# schematic_kcs-01r.net
KiCad netlist of a schematic drawn in EasyEDA
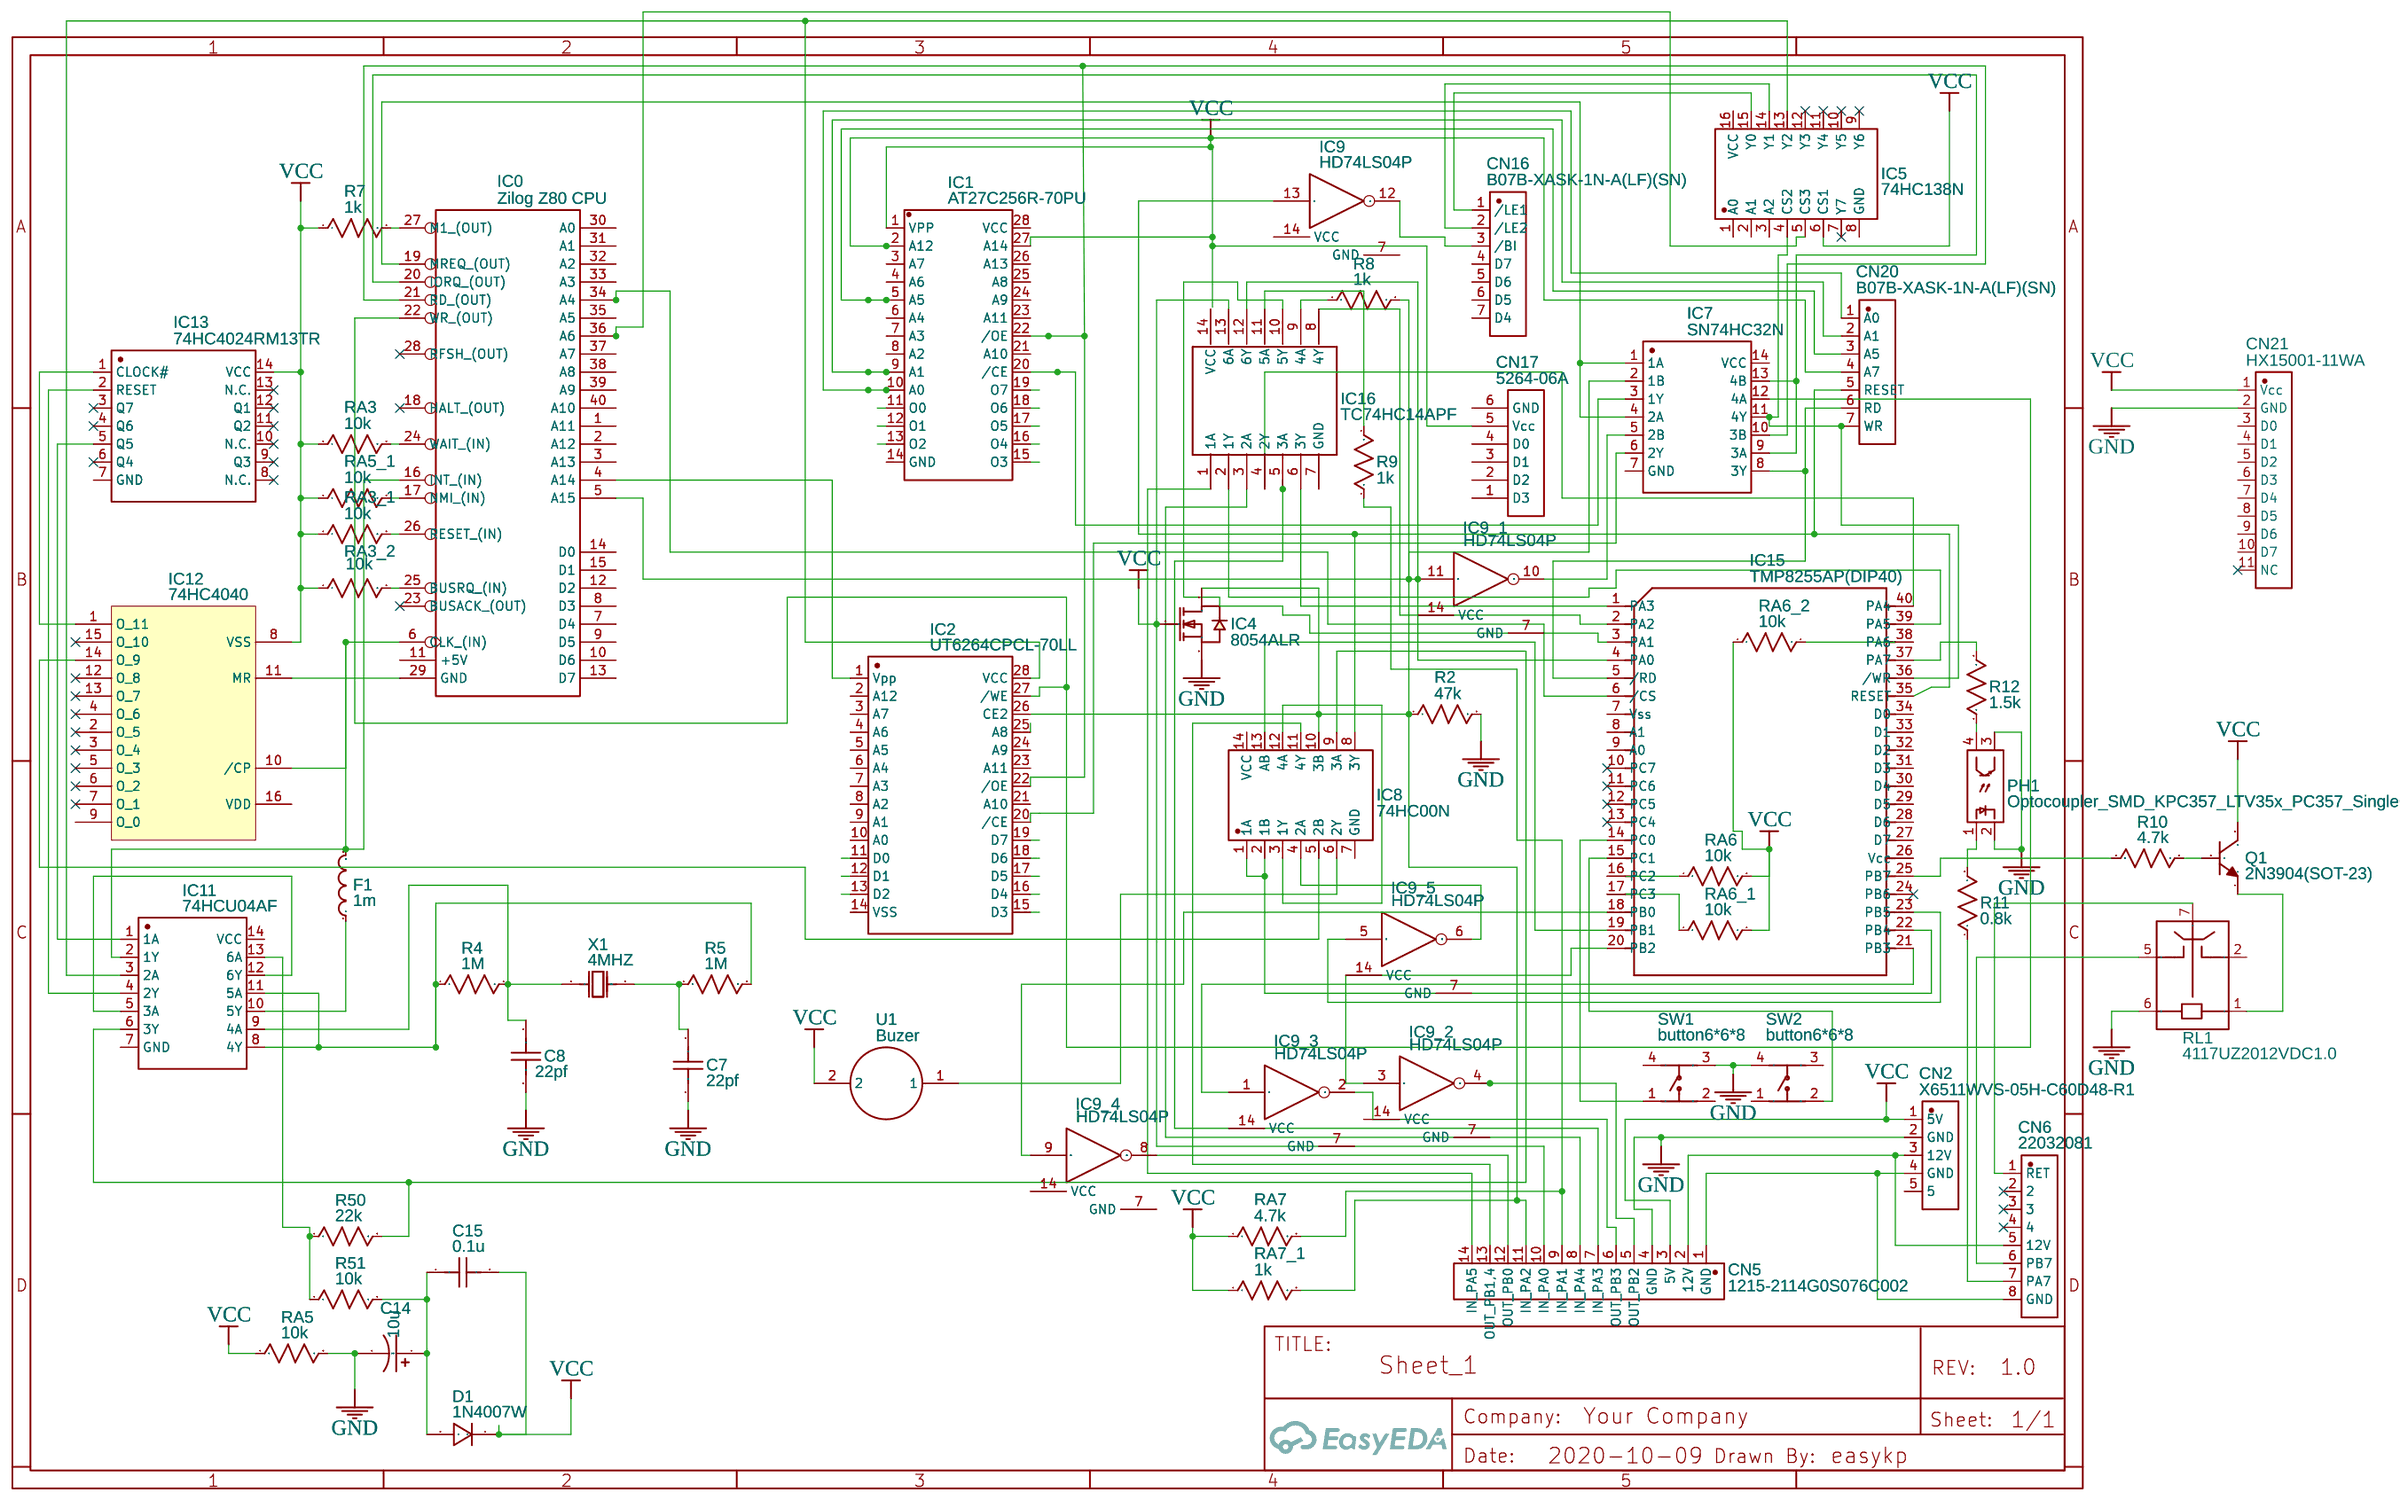
[diagram p0: schematic sheet]

(export (version "E")
  (design (tool "Eeschema 10.0.6"))
  (components
    (comp (ref "C7") (value "22pf") (libsource (lib "") (part "C_0603_US")))
    (comp (ref "C8") (value "22pf") (libsource (lib "") (part "C_0603_US")))
    (comp (ref "C14") (value "10u") (libsource (lib "") (part "C_Tan_SMD_A_US")))
    (comp (ref "C15") (value "0.1u") (libsource (lib "") (part "C_0603_US_1")))
    (comp (ref "CN2")
      (value "X6511WVS-05H-C60D48-R1")
      (fields (field (name "BOM_Supplier Part") "C780063"))
      (libsource (lib "") (part "X6511WVS-05H-C60D48-R1"))
    )
    (comp (ref "CN5")
      (value "1215-2114G0S076C002")
      (fields (field (name "BOM_Supplier Part") "C721461"))
      (libsource (lib "") (part "1215-2114G0S076C002"))
    )
    (comp (ref "CN6")
      (value "22032081")
      (fields (field (name "BOM_Supplier Part") "C586971"))
      (libsource (lib "") (part "22032081"))
    )
    (comp (ref "CN16")
      (value "B07B-XASK-1N-A(LF)(SN)")
      (fields (field (name "BOM_Supplier Part") "C378921"))
      (libsource (lib "") (part "B07B-XASK-1N-A(LF)(SN)_1"))
    )
    (comp (ref "CN17")
      (value "5264-06A")
      (fields (field (name "BOM_Supplier Part") "C40160"))
      (libsource (lib "") (part "5264-06A"))
    )
    (comp (ref "CN20")
      (value "B07B-XASK-1N-A(LF)(SN)")
      (fields (field (name "BOM_Supplier Part") "C378921"))
      (libsource (lib "") (part "B07B-XASK-1N-A(LF)(SN)"))
    )
    (comp (ref "CN21")
      (value "HX15001-11WA")
      (fields (field (name "BOM_Supplier Part") "C442136"))
      (libsource (lib "") (part "HX15001-11WA"))
    )
    (comp (ref "D1")
      (value "1N4007W")
      (fields (field (name "BOM_Supplier Part") "C328592"))
      (libsource (lib "") (part "1N4007W"))
    )
    (comp (ref "F1") (value "1m") (libsource (lib "") (part "L0603_US")))
    (comp (ref "IC0")
      (value "Zilog Z80 CPU")
      (fields (field (name "BOM_Manufacturer Part") "Zilog") (field (name "BOM_Supplier Part") "Z84C0020"))
      (libsource (lib "") (part "Zilog Z80 CPU"))
    )
    (comp (ref "IC1")
      (value "AT27C256R-70PU")
      (fields (field (name "BOM_Supplier Part") "C147880"))
      (libsource (lib "") (part "AT27C256R-70PU"))
    )
    (comp (ref "IC2")
      (value "UT6264CPCL-70LL")
      (fields (field (name "BOM_Supplier Part") "C32483"))
      (libsource (lib "") (part "UT6264CPCL-70LL"))
    )
    (comp (ref "IC4") (value "8054ALR") (libsource (lib "") (part "2N7002")))
    (comp (ref "IC5")
      (value "74HC138N")
      (fields (field (name "BOM_Supplier Part") "C507188"))
      (libsource (lib "") (part "74HC138N"))
    )
    (comp (ref "IC7")
      (value "SN74HC32N")
      (fields (field (name "BOM_Supplier Part") "C2894"))
      (libsource (lib "") (part "SN74HC32N"))
    )
    (comp (ref "IC8")
      (value "74HC00N")
      (fields (field (name "BOM_Supplier Part") "C596352"))
      (libsource (lib "") (part "74HC00N"))
    )
    (comp (ref "IC9") (value "HD74LS04P") (libsource (lib "") (part "HD74LS04P_2")))
    (comp (ref "IC9_1") (value "HD74LS04P") (libsource (lib "") (part "HD74LS04P_1")))
    (comp (ref "IC9_2") (value "HD74LS04P") (libsource (lib "") (part "HD74LS04P_5")))
    (comp (ref "IC9_3") (value "HD74LS04P") (libsource (lib "") (part "HD74LS04P")))
    (comp (ref "IC9_4") (value "HD74LS04P") (libsource (lib "") (part "HD74LS04P_4")))
    (comp (ref "IC9_5") (value "HD74LS04P") (libsource (lib "") (part "HD74LS04P_3")))
    (comp (ref "IC11")
      (value "74HCU04AF")
      (fields (field (name "BOM_Supplier Part") "C8157"))
      (libsource (lib "") (part "74HCU04AF"))
    )
    (comp (ref "IC12") (value "74HC4040") (libsource (lib "") (part "74HC4040")))
    (comp (ref "IC13")
      (value "74HC4024RM13TR")
      (fields (field (name "BOM_Supplier Part") "C5643"))
      (libsource (lib "") (part "74HC4024RM13TR"))
    )
    (comp (ref "IC15")
      (value "TMP8255AP(DIP40)")
      (fields (field (name "BOM_Manufacturer Part") "?"))
      (libsource (lib "") (part "MCU-ATMEGA32-16PU(DIP40)"))
    )
    (comp (ref "IC16") (value "TC74HC14APF") (libsource (lib "") (part "TC74HC14APF")))
    (comp (ref "PH1")
      (value "Optocoupler_SMD_KPC357_LTV35x_PC357_SingleChannel")
      (libsource (lib "") (part "Optocoupler_SMD_KPC357_LTV35x_PC357_SingleChannel"))
    )
    (comp (ref "Q1")
      (value "2N3904(SOT-23)")
      (fields
        (field (name "BOM_Manufacturer Part") "2n3904S-RTK/PS")
        (field (name "BOM_Supplier Part") "C18536")
      )
      (libsource (lib "") (part "2N3904(SOT-23)"))
    )
    (comp (ref "R2") (value "47k") (libsource (lib "") (part "R_0603_US")))
    (comp (ref "R4") (value "1M") (libsource (lib "") (part "R_0603_US")))
    (comp (ref "R5") (value "1M") (libsource (lib "") (part "R_0603_US")))
    (comp (ref "R7") (value "1k") (libsource (lib "") (part "R_0603_US")))
    (comp (ref "R8") (value "1k") (libsource (lib "") (part "R_0603_US")))
    (comp (ref "R9") (value "1k") (libsource (lib "") (part "R_0603_US_1")))
    (comp (ref "R10") (value "4.7k") (libsource (lib "") (part "R_0603_US_6")))
    (comp (ref "R11") (value "0.8k") (libsource (lib "") (part "R_0603_US_1")))
    (comp (ref "R12") (value "1.5k") (libsource (lib "") (part "R_0603_US_1")))
    (comp (ref "R50") (value "22k") (libsource (lib "") (part "R_0603_US")))
    (comp (ref "R51") (value "10k") (libsource (lib "") (part "R_0603_US")))
    (comp (ref "RA3") (value "10k") (libsource (lib "") (part "R_0603_US_5")))
    (comp (ref "RA3_1") (value "10k") (libsource (lib "") (part "R_0603_US_3")))
    (comp (ref "RA3_2") (value "10k") (libsource (lib "") (part "R_0603_US_3")))
    (comp (ref "RA5") (value "10k") (libsource (lib "") (part "R_0603_US_5")))
    (comp (ref "RA5_1") (value "10k") (libsource (lib "") (part "R_0603_US_7")))
    (comp (ref "RA6") (value "10k") (libsource (lib "") (part "R_0603_US_5")))
    (comp (ref "RA6_1") (value "10k") (libsource (lib "") (part "R_0603_US_4")))
    (comp (ref "RA6_2") (value "10k") (libsource (lib "") (part "R_0603_US_4")))
    (comp (ref "RA7") (value "4.7k") (libsource (lib "") (part "R_0603_US_5")))
    (comp (ref "RA7_1") (value "1k") (libsource (lib "") (part "R_0603_US_2")))
    (comp (ref "RL1")
      (value "4117UZ2012VDC1.0")
      (fields (field (name "BOM_Supplier Part") "C165875"))
      (libsource (lib "") (part "4117UZ2012VDC1.0"))
    )
    (comp (ref "SW1")
      (value "button6*6*8")
      (fields (field (name "BOM_Supplier Part") "C59982"))
      (libsource (lib "") (part "button6*6*8"))
    )
    (comp (ref "SW2")
      (value "button6*6*8")
      (fields (field (name "BOM_Supplier Part") "C59982"))
      (libsource (lib "") (part "button6*6*8"))
    )
    (comp (ref "U1") (value "Buzer") (libsource (lib "") (part "Buzer")))
    (comp (ref "X1")
      (value "4MHZ")
      (fields
        (field (name "BOM_Manufacturer Part") "49SAC04000202080")
        (field (name "BOM_Supplier Part") "C390748")
      )
      (libsource (lib "") (part "49SAC04000202080"))
    )
  )
  (nets
    (net (code "1") (name "GND") (class "Default")
      (node (ref "C14") (pin "2") (pinfunction "2_2") (pintype "unspecified"))
      (node (ref "C7") (pin "1") (pinfunction "1_1") (pintype "unspecified"))
      (node (ref "C8") (pin "1") (pinfunction "1_1") (pintype "unspecified"))
      (node (ref "CN2") (pin "2") (pinfunction "GND_2") (pintype "unspecified"))
      (node (ref "CN21") (pin "2") (pinfunction "GND_2") (pintype "unspecified"))
      (node (ref "CN5") (pin "4") (pinfunction "GND_4") (pintype "unspecified"))
      (node (ref "IC4") (pin "2") (pinfunction "S_2") (pintype "unspecified"))
      (node (ref "PH1") (pin "2") (pintype "unspecified"))
      (node (ref "PH1") (pin "3") (pintype "unspecified"))
      (node (ref "R2") (pin "2") (pinfunction "2_2") (pintype "unspecified"))
      (node (ref "RA5") (pin "2") (pinfunction "2_2") (pintype "unspecified"))
      (node (ref "RL1") (pin "6") (pinfunction "6_6") (pintype "unspecified"))
      (node (ref "SW1") (pin "3") (pinfunction "3_3") (pintype "unspecified"))
      (node (ref "SW2") (pin "4") (pinfunction "4_4") (pintype "unspecified"))
    )
    (net (code "2") (name "Net-(C14-Pad1)") (class "Default")
      (node (ref "C14") (pin "1") (pinfunction "1_1") (pintype "unspecified"))
      (node (ref "C15") (pin "1") (pinfunction "1_1") (pintype "unspecified"))
      (node (ref "D1") (pin "2") (pinfunction "2_2") (pintype "unspecified"))
      (node (ref "R51") (pin "2") (pinfunction "2_2") (pintype "unspecified"))
    )
    (net (code "3") (name "Net-(CN2-12V)") (class "Default")
      (node (ref "CN2") (pin "3") (pinfunction "12V_3") (pintype "unspecified"))
      (node (ref "CN5") (pin "2") (pinfunction "12V_2") (pintype "unspecified"))
      (node (ref "CN6") (pin "5") (pinfunction "12V_5") (pintype "unspecified"))
    )
    (net (code "4") (name "Net-(CN5-IN_PA1)") (class "Default")
      (node (ref "CN5") (pin "9") (pinfunction "IN_PA1_9") (pintype "unspecified"))
      (node (ref "R9") (pin "1") (pinfunction "1_1") (pintype "unspecified"))
      (node (ref "RA7") (pin "2") (pinfunction "2_2") (pintype "unspecified"))
    )
    (net (code "5") (name "Net-(CN5-IN_PA2)") (class "Default")
      (node (ref "CN5") (pin "11") (pinfunction "IN_PA2_11") (pintype "unspecified"))
      (node (ref "IC0") (pin "5") (pinfunction "A15_5") (pintype "output"))
      (node (ref "IC15") (pin "4") (pinfunction "PA0_4") (pintype "unspecified"))
      (node (ref "IC16") (pin "12") (pinfunction "6Y_12") (pintype "bidirectional"))
      (node (ref "IC2") (pin "26") (pinfunction "CE2_26") (pintype "unspecified"))
      (node (ref "IC4") (pin "3") (pinfunction "D_3") (pintype "unspecified"))
      (node (ref "IC7") (pin "2") (pinfunction "1B_2") (pintype "unspecified"))
      (node (ref "IC8") (pin "10") (pinfunction "3B_10") (pintype "unspecified"))
      (node (ref "IC9_1") (pin "11") (pinfunction "6A_11") (pintype "unspecified"))
      (node (ref "R2") (pin "1") (pinfunction "1_1") (pintype "unspecified"))
      (node (ref "R8") (pin "2") (pinfunction "2_2") (pintype "unspecified"))
      (node (ref "RA7_1") (pin "2") (pinfunction "2_2") (pintype "unspecified"))
    )
    (net (code "6") (name "Net-(CN5-IN_PA3)") (class "Default")
      (node (ref "CN5") (pin "7") (pinfunction "IN_PA3_7") (pintype "unspecified"))
      (node (ref "IC16") (pin "5") (pinfunction "3A_5") (pintype "bidirectional"))
    )
    (net (code "7") (name "Net-(CN5-IN_PA4)") (class "Default")
      (node (ref "CN5") (pin "8") (pinfunction "IN_PA4_8") (pintype "unspecified"))
      (node (ref "IC16") (pin "3") (pinfunction "2A_3") (pintype "bidirectional"))
    )
    (net (code "8") (name "Net-(CN5-IN_PA5)") (class "Default")
      (node (ref "CN5") (pin "14") (pinfunction "IN_PA5_14") (pintype "unspecified"))
      (node (ref "IC16") (pin "1") (pinfunction "1A_1") (pintype "bidirectional"))
    )
    (net (code "9") (name "Net-(CN5-OUT_PB0)") (class "Default")
      (node (ref "CN5") (pin "12") (pinfunction "OUT_PB0_12") (pintype "unspecified"))
      (node (ref "IC9_4") (pin "8") (pinfunction "6Y_8") (pintype "output"))
    )
    (net (code "10") (name "Net-(CN5-OUT_PB1,4)") (class "Default")
      (node (ref "CN5") (pin "13") (pinfunction "OUT_PB1,4_13") (pintype "unspecified"))
      (node (ref "IC8") (pin "11") (pinfunction "4Y_11") (pintype "unspecified"))
    )
    (net (code "11") (name "Net-(CN5-OUT_PB2)") (class "Default")
      (node (ref "CN5") (pin "5") (pinfunction "OUT_PB2_5") (pintype "unspecified"))
      (node (ref "IC9_2") (pin "4") (pinfunction "6Y_4") (pintype "output"))
    )
    (net (code "12") (name "Net-(CN5-OUT_PB3)") (class "Default")
      (node (ref "CN5") (pin "6") (pinfunction "OUT_PB3_6") (pintype "unspecified"))
      (node (ref "IC9_3") (pin "2") (pinfunction "6Y_2") (pintype "output"))
    )
    (net (code "13") (name "Net-(CN6-GND)") (class "Default")
      (node (ref "CN2") (pin "4") (pinfunction "GND_4") (pintype "unspecified"))
      (node (ref "CN5") (pin "1") (pinfunction "GND_1") (pintype "unspecified"))
      (node (ref "CN6") (pin "8") (pinfunction "GND_8") (pintype "unspecified"))
    )
    (net (code "14") (name "Net-(CN6-PA7)") (class "Default")
      (node (ref "CN6") (pin "7") (pinfunction "PA7_7") (pintype "unspecified"))
      (node (ref "R11") (pin "1") (pinfunction "1_1") (pintype "unspecified"))
    )
    (net (code "15") (name "Net-(CN6-PB7)") (class "Default")
      (node (ref "CN6") (pin "6") (pinfunction "PB7_6") (pintype "unspecified"))
      (node (ref "RL1") (pin "5") (pinfunction "5_5") (pintype "unspecified"))
    )
    (net (code "16") (name "Net-(CN6-RET)") (class "Default")
      (node (ref "CN6") (pin "1") (pinfunction "RET_1") (pintype "unspecified"))
      (node (ref "RL1") (pin "7") (pinfunction "7_7") (pintype "unspecified"))
    )
    (net (code "17") (name "Net-(CN16-{slash}BI)") (class "Default")
      (node (ref "CN16") (pin "3") (pinfunction "/BI_3") (pintype "unspecified"))
      (node (ref "IC9") (pin "12") (pinfunction "6Y_12") (pintype "output"))
    )
    (net (code "18") (name "Net-(CN16-{slash}LE1)") (class "Default")
      (node (ref "CN16") (pin "1") (pinfunction "/LE1_1") (pintype "unspecified"))
      (node (ref "IC5") (pin "15") (pinfunction "Y0_15") (pintype "unspecified"))
    )
    (net (code "19") (name "Net-(CN16-{slash}LE2)") (class "Default")
      (node (ref "CN16") (pin "2") (pinfunction "/LE2_2") (pintype "unspecified"))
      (node (ref "IC5") (pin "14") (pinfunction "Y1_14") (pintype "unspecified"))
    )
    (net (code "20") (name "Net-(CN20-A0)") (class "Default")
      (node (ref "CN20") (pin "1") (pinfunction "A0_1") (pintype "unspecified"))
      (node (ref "IC1") (pin "10") (pinfunction "A0_10") (pintype "unspecified"))
    )
    (net (code "21") (name "Net-(CN20-A1)") (class "Default")
      (node (ref "CN20") (pin "2") (pinfunction "A1_2") (pintype "unspecified"))
      (node (ref "IC1") (pin "9") (pinfunction "A1_9") (pintype "unspecified"))
    )
    (net (code "22") (name "Net-(CN20-A5)") (class "Default")
      (node (ref "CN20") (pin "3") (pinfunction "A5_3") (pintype "unspecified"))
      (node (ref "IC1") (pin "5") (pinfunction "A5_5") (pintype "unspecified"))
    )
    (net (code "23") (name "Net-(CN20-RD)") (class "Default")
      (node (ref "CN20") (pin "6") (pinfunction "RD_6") (pintype "unspecified"))
      (node (ref "IC15") (pin "5") (pinfunction "/RD_5") (pintype "unspecified"))
      (node (ref "IC7") (pin "8") (pinfunction "3Y_8") (pintype "unspecified"))
    )
    (net (code "24") (name "Net-(CN20-RESET)") (class "Default")
      (node (ref "CN20") (pin "5") (pinfunction "RESET_5") (pintype "unspecified"))
      (node (ref "IC15") (pin "35") (pinfunction "RESET_35") (pintype "unspecified"))
      (node (ref "IC8") (pin "8") (pinfunction "3Y_8") (pintype "unspecified"))
      (node (ref "IC9") (pin "13") (pinfunction "6A_13") (pintype "unspecified"))
    )
    (net (code "25") (name "Net-(CN20-WR)") (class "Default")
      (node (ref "CN20") (pin "7") (pinfunction "WR_7") (pintype "unspecified"))
      (node (ref "IC0") (pin "36") (pinfunction "A6_36") (pintype "output"))
      (node (ref "IC15") (pin "36") (pinfunction "/WR_36") (pintype "unspecified"))
      (node (ref "IC5") (pin "4") (pinfunction "CS2_4") (pintype "unspecified"))
      (node (ref "IC5") (pin "5") (pinfunction "CS3_5") (pintype "unspecified"))
      (node (ref "IC7") (pin "11") (pinfunction "4Y_11") (pintype "unspecified"))
    )
    (net (code "26") (name "Net-(IC0-A4)") (class "Default")
      (node (ref "IC0") (pin "34") (pinfunction "A4_34") (pintype "output"))
      (node (ref "IC15") (pin "6") (pinfunction "/CS_6") (pintype "unspecified"))
    )
    (net (code "27") (name "Net-(IC0-A14)") (class "Default")
      (node (ref "IC0") (pin "4") (pinfunction "A14_4") (pintype "output"))
      (node (ref "IC2") (pin "1") (pinfunction "Vpp_1") (pintype "unspecified"))
    )
    (net (code "28") (name "Net-(IC0-BUSRQ_(IN))") (class "Default")
      (node (ref "IC0") (pin "25") (pinfunction "BUSRQ_(IN)_25") (pintype "input"))
      (node (ref "RA3_2") (pin "2") (pinfunction "2_2") (pintype "unspecified"))
    )
    (net (code "29") (name "Net-(IC0-CLK_(IN))") (class "Default")
      (node (ref "F1") (pin "2") (pinfunction "2_2") (pintype "unspecified"))
      (node (ref "IC0") (pin "16") (pinfunction "INT_(IN)_16") (pintype "input"))
      (node (ref "IC0") (pin "6") (pinfunction "CLK_(IN)_6") (pintype "input"))
      (node (ref "IC11") (pin "2") (pinfunction "1Y_2") (pintype "unspecified"))
      (node (ref "IC12") (pin "10") (pinfunction "/CP_10") (pintype "unspecified"))
    )
    (net (code "30") (name "Net-(IC0-GND)") (class "Default")
      (node (ref "IC0") (pin "29") (pinfunction "GND_29") (pintype "passive"))
      (node (ref "IC12") (pin "11") (pinfunction "MR_11") (pintype "unspecified"))
    )
    (net (code "31") (name "Net-(IC0-IORQ_(OUT))") (class "Default")
      (node (ref "IC0") (pin "20") (pinfunction "IORQ_(OUT)_20") (pintype "output"))
      (node (ref "IC7") (pin "13") (pinfunction "4B_13") (pintype "unspecified"))
      (node (ref "IC7") (pin "9") (pinfunction "3A_9") (pintype "unspecified"))
    )
    (net (code "32") (name "Net-(IC0-M1_(OUT))") (class "Default")
      (node (ref "IC0") (pin "27") (pinfunction "M1_(OUT)_27") (pintype "output"))
      (node (ref "R7") (pin "2") (pinfunction "2_2") (pintype "unspecified"))
    )
    (net (code "33") (name "Net-(IC0-MREQ_(OUT))") (class "Default")
      (node (ref "IC0") (pin "19") (pinfunction "MREQ_(OUT)_19") (pintype "output"))
      (node (ref "IC7") (pin "1") (pinfunction "1A_1") (pintype "unspecified"))
      (node (ref "IC7") (pin "4") (pinfunction "2A_4") (pintype "unspecified"))
    )
    (net (code "34") (name "Net-(IC0-NMI_(IN))") (class "Default")
      (node (ref "IC0") (pin "17") (pinfunction "NMI_(IN)_17") (pintype "input"))
      (node (ref "RA5_1") (pin "2") (pinfunction "2_2") (pintype "unspecified"))
    )
    (net (code "35") (name "Net-(IC0-RD_(OUT))") (class "Default")
      (node (ref "IC0") (pin "21") (pinfunction "RD_(OUT)_21") (pintype "output"))
      (node (ref "IC1") (pin "22") (pinfunction "/OE_22") (pintype "unspecified"))
      (node (ref "IC2") (pin "22") (pinfunction "/OE_22") (pintype "unspecified"))
      (node (ref "IC7") (pin "10") (pinfunction "3B_10") (pintype "unspecified"))
    )
    (net (code "36") (name "Net-(IC0-RESET_(IN))") (class "Default")
      (node (ref "IC0") (pin "26") (pinfunction "RESET_(IN)_26") (pintype "input"))
      (node (ref "RA3_1") (pin "2") (pinfunction "2_2") (pintype "unspecified"))
    )
    (net (code "37") (name "Net-(IC0-WAIT_(IN))") (class "Default")
      (node (ref "IC0") (pin "24") (pinfunction "WAIT_(IN)_24") (pintype "input"))
      (node (ref "RA3") (pin "2") (pinfunction "2_2") (pintype "unspecified"))
    )
    (net (code "38") (name "Net-(IC0-WR_(OUT))") (class "Default")
      (node (ref "IC0") (pin "22") (pinfunction "WR_(OUT)_22") (pintype "output"))
      (node (ref "IC2") (pin "27") (pinfunction "/WE_27") (pintype "unspecified"))
      (node (ref "IC7") (pin "12") (pinfunction "4A_12") (pintype "unspecified"))
    )
    (net (code "39") (name "Net-(IC1-{slash}CE)") (class "Default")
      (node (ref "IC1") (pin "20") (pinfunction "/CE_20") (pintype "unspecified"))
      (node (ref "IC7") (pin "3") (pinfunction "1Y_3") (pintype "unspecified"))
    )
    (net (code "40") (name "Net-(IC2-{slash}CE)") (class "Default")
      (node (ref "IC2") (pin "20") (pinfunction "/CE_20") (pintype "unspecified"))
      (node (ref "IC7") (pin "6") (pinfunction "2Y_6") (pintype "unspecified"))
    )
    (net (code "41") (name "Net-(IC7-2B)") (class "Default")
      (node (ref "IC7") (pin "5") (pinfunction "2B_5") (pintype "unspecified"))
      (node (ref "IC9_1") (pin "10") (pinfunction "6Y_10") (pintype "output"))
    )
    (net (code "42") (name "Net-(IC8-1Y)") (class "Default")
      (node (ref "IC8") (pin "12") (pinfunction "4A_12") (pintype "unspecified"))
      (node (ref "IC8") (pin "3") (pinfunction "1Y_3") (pintype "unspecified"))
    )
    (net (code "43") (name "Net-(IC8-2A)") (class "Default")
      (node (ref "IC8") (pin "4") (pinfunction "2A_4") (pintype "unspecified"))
      (node (ref "IC9_5") (pin "6") (pinfunction "6Y_6") (pintype "output"))
    )
    (net (code "44") (name "Net-(IC8-2Y)") (class "Default")
      (node (ref "IC8") (pin "6") (pinfunction "2Y_6") (pintype "unspecified"))
      (node (ref "U1") (pin "1") (pinfunction "1_1") (pintype "unspecified"))
    )
    (net (code "45") (name "Net-(IC11-1A)") (class "Default")
      (node (ref "IC11") (pin "1") (pinfunction "1A_1") (pintype "unspecified"))
      (node (ref "IC13") (pin "5") (pinfunction "Q5_5") (pintype "unspecified"))
    )
    (net (code "46") (name "Net-(IC11-2A)") (class "Default")
      (node (ref "IC11") (pin "3") (pinfunction "2A_3") (pintype "unspecified"))
      (node (ref "IC2") (pin "28") (pinfunction "VCC_28") (pintype "unspecified"))
      (node (ref "IC5") (pin "13") (pinfunction "Y2_13") (pintype "unspecified"))
    )
    (net (code "47") (name "Net-(IC11-2Y)") (class "Default")
      (node (ref "IC11") (pin "4") (pinfunction "2Y_4") (pintype "unspecified"))
      (node (ref "IC13") (pin "2") (pinfunction "RESET_2") (pintype "unspecified"))
    )
    (net (code "48") (name "Net-(IC11-3A)") (class "Default")
      (node (ref "IC11") (pin "12") (pinfunction "6Y_12") (pintype "unspecified"))
      (node (ref "IC11") (pin "5") (pinfunction "3A_5") (pintype "unspecified"))
    )
    (net (code "49") (name "Net-(IC11-3Y)") (class "Default")
      (node (ref "IC11") (pin "6") (pinfunction "3Y_6") (pintype "unspecified"))
      (node (ref "IC8") (pin "9") (pinfunction "3A_9") (pintype "unspecified"))
      (node (ref "R50") (pin "2") (pinfunction "2_2") (pintype "unspecified"))
    )
    (net (code "50") (name "Net-(IC11-4A)") (class "Default")
      (node (ref "C8") (pin "2") (pinfunction "2_2") (pintype "unspecified"))
      (node (ref "IC11") (pin "9") (pinfunction "4A_9") (pintype "unspecified"))
      (node (ref "R4") (pin "2") (pinfunction "2_2") (pintype "unspecified"))
      (node (ref "X1") (pin "1") (pinfunction "OSC1_1") (pintype "input"))
    )
    (net (code "51") (name "Net-(IC11-4Y)") (class "Default")
      (node (ref "IC11") (pin "11") (pinfunction "5A_11") (pintype "unspecified"))
      (node (ref "IC11") (pin "8") (pinfunction "4Y_8") (pintype "unspecified"))
      (node (ref "R4") (pin "1") (pinfunction "1_1") (pintype "unspecified"))
      (node (ref "R5") (pin "2") (pinfunction "2_2") (pintype "unspecified"))
    )
    (net (code "52") (name "Net-(IC11-5Y)") (class "Default")
      (node (ref "F1") (pin "1") (pinfunction "1_1") (pintype "unspecified"))
      (node (ref "IC11") (pin "10") (pinfunction "5Y_10") (pintype "unspecified"))
    )
    (net (code "53") (name "Net-(IC11-6A)") (class "Default")
      (node (ref "IC11") (pin "13") (pinfunction "6A_13") (pintype "unspecified"))
      (node (ref "R50") (pin "1") (pinfunction "1_1") (pintype "unspecified"))
      (node (ref "R51") (pin "1") (pinfunction "1_1") (pintype "unspecified"))
    )
    (net (code "54") (name "Net-(IC12-O_9)") (class "Default")
      (node (ref "IC12") (pin "14") (pinfunction "O_9_14") (pintype "unspecified"))
      (node (ref "IC8") (pin "5") (pinfunction "2B_5") (pintype "unspecified"))
    )
    (net (code "55") (name "Net-(IC12-O_11)") (class "Default")
      (node (ref "IC12") (pin "1") (pinfunction "O_11_1") (pintype "unspecified"))
      (node (ref "IC13") (pin "1") (pinfunction "CLOCK#_1") (pintype "unspecified"))
    )
    (net (code "56") (name "Net-(IC15-PA1)") (class "Default")
      (node (ref "IC15") (pin "3") (pinfunction "PA1_3") (pintype "unspecified"))
      (node (ref "IC16") (pin "10") (pinfunction "5Y_10") (pintype "bidirectional"))
    )
    (net (code "57") (name "Net-(IC15-PA2)") (class "Default")
      (node (ref "IC15") (pin "2") (pinfunction "PA2_2") (pintype "unspecified"))
      (node (ref "IC16") (pin "8") (pinfunction "4Y_8") (pintype "bidirectional"))
    )
    (net (code "58") (name "Net-(IC15-PA3)") (class "Default")
      (node (ref "IC15") (pin "1") (pinfunction "PA3_1") (pintype "unspecified"))
      (node (ref "IC16") (pin "6") (pinfunction "3Y_6") (pintype "bidirectional"))
    )
    (net (code "59") (name "Net-(IC15-PA4)") (class "Default")
      (node (ref "IC15") (pin "40") (pinfunction "PA4_40") (pintype "unspecified"))
      (node (ref "IC16") (pin "4") (pinfunction "2Y_4") (pintype "bidirectional"))
    )
    (net (code "60") (name "Net-(IC15-PA5)") (class "Default")
      (node (ref "IC15") (pin "39") (pinfunction "PA5_39") (pintype "unspecified"))
      (node (ref "IC16") (pin "2") (pinfunction "1Y_2") (pintype "bidirectional"))
    )
    (net (code "61") (name "Net-(IC15-PA6)") (class "Default")
      (node (ref "IC15") (pin "38") (pinfunction "PA6_38") (pintype "unspecified"))
      (node (ref "RA6_2") (pin "2") (pinfunction "2_2") (pintype "unspecified"))
    )
    (net (code "62") (name "Net-(IC15-PA7)") (class "Default")
      (node (ref "IC15") (pin "37") (pinfunction "PA7_37") (pintype "unspecified"))
      (node (ref "R12") (pin "2") (pinfunction "2_2") (pintype "unspecified"))
    )
    (net (code "63") (name "Net-(IC15-PB0)") (class "Default")
      (node (ref "IC15") (pin "18") (pinfunction "PB0_18") (pintype "unspecified"))
      (node (ref "IC9_4") (pin "9") (pinfunction "6A_9") (pintype "unspecified"))
    )
    (net (code "64") (name "Net-(IC15-PB1)") (class "Default")
      (node (ref "IC15") (pin "19") (pinfunction "PB1_19") (pintype "unspecified"))
      (node (ref "IC8") (pin "13") (pinfunction "AB_13") (pintype "unspecified"))
    )
    (net (code "65") (name "Net-(IC15-PB2)") (class "Default")
      (node (ref "IC15") (pin "20") (pinfunction "PB2_20") (pintype "unspecified"))
      (node (ref "IC9_2") (pin "3") (pinfunction "6A_3") (pintype "unspecified"))
      (node (ref "IC9_5") (pin "14") (pinfunction "VCC_14") (pintype "passive"))
    )
    (net (code "66") (name "Net-(IC15-PB3)") (class "Default")
      (node (ref "IC15") (pin "21") (pinfunction "PB3_21") (pintype "unspecified"))
      (node (ref "IC9_3") (pin "1") (pinfunction "6A_1") (pintype "unspecified"))
    )
    (net (code "67") (name "Net-(IC15-PB4)") (class "Default")
      (node (ref "IC15") (pin "22") (pinfunction "PB4_22") (pintype "unspecified"))
      (node (ref "IC8") (pin "1") (pinfunction "1A_1") (pintype "unspecified"))
      (node (ref "IC8") (pin "2") (pinfunction "1B_2") (pintype "unspecified"))
    )
    (net (code "68") (name "Net-(IC15-PB5)") (class "Default")
      (node (ref "IC15") (pin "23") (pinfunction "PB5_23") (pintype "unspecified"))
      (node (ref "IC9_5") (pin "5") (pinfunction "6A_5") (pintype "unspecified"))
    )
    (net (code "69") (name "Net-(IC15-PB7)") (class "Default")
      (node (ref "IC15") (pin "25") (pinfunction "PB7_25") (pintype "unspecified"))
      (node (ref "R10") (pin "2") (pinfunction "2_2") (pintype "unspecified"))
    )
    (net (code "70") (name "Net-(IC15-PC0)") (class "Default")
      (node (ref "IC15") (pin "14") (pinfunction "PC0_14") (pintype "unspecified"))
      (node (ref "SW1") (pin "1") (pinfunction "1_1") (pintype "unspecified"))
    )
    (net (code "71") (name "Net-(IC15-PC1)") (class "Default")
      (node (ref "IC15") (pin "15") (pinfunction "PC1_15") (pintype "unspecified"))
      (node (ref "SW2") (pin "2") (pinfunction "2_2") (pintype "unspecified"))
    )
    (net (code "72") (name "Net-(IC15-PC2)") (class "Default")
      (node (ref "IC15") (pin "16") (pinfunction "PC2_16") (pintype "unspecified"))
      (node (ref "RA6") (pin "1") (pinfunction "1_1") (pintype "unspecified"))
    )
    (net (code "73") (name "Net-(IC15-PC3)") (class "Default")
      (node (ref "IC15") (pin "17") (pinfunction "PC3_17") (pintype "unspecified"))
      (node (ref "RA6_1") (pin "1") (pinfunction "1_1") (pintype "unspecified"))
    )
    (net (code "74") (name "Net-(IC16-4A)") (class "Default")
      (node (ref "IC16") (pin "9") (pinfunction "4A_9") (pintype "bidirectional"))
      (node (ref "R8") (pin "1") (pinfunction "1_1") (pintype "unspecified"))
    )
    (net (code "75") (name "Net-(IC16-5A)") (class "Default")
      (node (ref "IC16") (pin "11") (pinfunction "5A_11") (pintype "bidirectional"))
      (node (ref "R9") (pin "2") (pinfunction "2_2") (pintype "unspecified"))
    )
    (net (code "76") (name "Net-(PH1-Pad1)") (class "Default")
      (node (ref "PH1") (pin "1") (pintype "unspecified"))
      (node (ref "R11") (pin "2") (pinfunction "2_2") (pintype "unspecified"))
    )
    (net (code "77") (name "Net-(PH1-Pad4)") (class "Default")
      (node (ref "PH1") (pin "4") (pintype "unspecified"))
      (node (ref "R12") (pin "1") (pinfunction "1_1") (pintype "unspecified"))
    )
    (net (code "78") (name "Net-(Q1-B)") (class "Default")
      (node (ref "Q1") (pin "2") (pinfunction "B_2") (pintype "input"))
      (node (ref "R10") (pin "1") (pinfunction "1_1") (pintype "unspecified"))
    )
    (net (code "79") (name "Net-(Q1-E)") (class "Default")
      (node (ref "Q1") (pin "1") (pinfunction "E_1") (pintype "input"))
      (node (ref "RL1") (pin "1") (pinfunction "1_1") (pintype "unspecified"))
    )
    (net (code "80") (name "Net-(X1-OSC2)") (class "Default")
      (node (ref "C7") (pin "2") (pinfunction "2_2") (pintype "unspecified"))
      (node (ref "R5") (pin "1") (pinfunction "1_1") (pintype "unspecified"))
      (node (ref "X1") (pin "2") (pinfunction "OSC2_2") (pintype "input"))
    )
    (net (code "81") (name "VCC") (class "Default")
      (node (ref "C15") (pin "2") (pinfunction "2_2") (pintype "unspecified"))
      (node (ref "CN17") (pin "5") (pinfunction "Vcc_5") (pintype "unspecified"))
      (node (ref "CN2") (pin "1") (pinfunction "5V_1") (pintype "unspecified"))
      (node (ref "CN20") (pin "4") (pinfunction "A7_4") (pintype "unspecified"))
      (node (ref "CN21") (pin "1") (pinfunction "Vcc_1") (pintype "unspecified"))
      (node (ref "CN5") (pin "10") (pinfunction "IN_PA0_10") (pintype "unspecified"))
      (node (ref "CN5") (pin "3") (pinfunction "5V_3") (pintype "unspecified"))
      (node (ref "D1") (pin "1") (pinfunction "1_1") (pintype "unspecified"))
      (node (ref "IC1") (pin "1") (pinfunction "VPP_1") (pintype "unspecified"))
      (node (ref "IC1") (pin "2") (pinfunction "A12_2") (pintype "unspecified"))
      (node (ref "IC1") (pin "27") (pinfunction "A14_27") (pintype "unspecified"))
      (node (ref "IC12") (pin "8") (pinfunction "VSS_8") (pintype "unspecified"))
      (node (ref "IC13") (pin "14") (pinfunction "VCC_14") (pintype "unspecified"))
      (node (ref "IC16") (pin "13") (pinfunction "6A_13") (pintype "bidirectional"))
      (node (ref "IC4") (pin "1") (pinfunction "G_1") (pintype "unspecified"))
      (node (ref "IC5") (pin "6") (pinfunction "CS1_6") (pintype "unspecified"))
      (node (ref "Q1") (pin "3") (pinfunction "C_3") (pintype "input"))
      (node (ref "R7") (pin "1") (pinfunction "1_1") (pintype "unspecified"))
      (node (ref "RA3") (pin "1") (pinfunction "1_1") (pintype "unspecified"))
      (node (ref "RA3_1") (pin "1") (pinfunction "1_1") (pintype "unspecified"))
      (node (ref "RA3_2") (pin "1") (pinfunction "1_1") (pintype "unspecified"))
      (node (ref "RA5") (pin "1") (pinfunction "1_1") (pintype "unspecified"))
      (node (ref "RA5_1") (pin "1") (pinfunction "1_1") (pintype "unspecified"))
      (node (ref "RA6") (pin "2") (pinfunction "2_2") (pintype "unspecified"))
      (node (ref "RA6_1") (pin "2") (pinfunction "2_2") (pintype "unspecified"))
      (node (ref "RA6_2") (pin "1") (pinfunction "1_1") (pintype "unspecified"))
      (node (ref "RA7") (pin "1") (pinfunction "1_1") (pintype "unspecified"))
      (node (ref "RA7_1") (pin "1") (pinfunction "1_1") (pintype "unspecified"))
      (node (ref "U1") (pin "2") (pinfunction "2_2") (pintype "unspecified"))
    )
    (net (code "82") (name "unconnected-(CN2-Pad5)") (class "Default")
      (node (ref "CN2") (pin "5") (pinfunction "5_5") (pintype "unspecified"))
    )
    (net (code "83") (name "unconnected-(CN6-Pad2)") (class "Default")
      (node (ref "CN6") (pin "2") (pinfunction "2_2") (pintype "unspecified+no_connect"))
    )
    (net (code "84") (name "unconnected-(CN6-Pad3)") (class "Default")
      (node (ref "CN6") (pin "3") (pinfunction "3_3") (pintype "unspecified+no_connect"))
    )
    (net (code "85") (name "unconnected-(CN6-Pad4)") (class "Default")
      (node (ref "CN6") (pin "4") (pinfunction "4_4") (pintype "unspecified+no_connect"))
    )
    (net (code "86") (name "unconnected-(CN16-D4-Pad7)") (class "Default")
      (node (ref "CN16") (pin "7") (pinfunction "D4_7") (pintype "unspecified"))
    )
    (net (code "87") (name "unconnected-(CN16-D5-Pad6)") (class "Default")
      (node (ref "CN16") (pin "6") (pinfunction "D5_6") (pintype "unspecified"))
    )
    (net (code "88") (name "unconnected-(CN16-D6-Pad5)") (class "Default")
      (node (ref "CN16") (pin "5") (pinfunction "D6_5") (pintype "unspecified"))
    )
    (net (code "89") (name "unconnected-(CN16-D7-Pad4)") (class "Default")
      (node (ref "CN16") (pin "4") (pinfunction "D7_4") (pintype "unspecified"))
    )
    (net (code "90") (name "unconnected-(CN17-D0-Pad4)") (class "Default")
      (node (ref "CN17") (pin "4") (pinfunction "D0_4") (pintype "unspecified"))
    )
    (net (code "91") (name "unconnected-(CN17-D1-Pad3)") (class "Default")
      (node (ref "CN17") (pin "3") (pinfunction "D1_3") (pintype "unspecified"))
    )
    (net (code "92") (name "unconnected-(CN17-D2-Pad2)") (class "Default")
      (node (ref "CN17") (pin "2") (pinfunction "D2_2") (pintype "unspecified"))
    )
    (net (code "93") (name "unconnected-(CN17-D3-Pad1)") (class "Default")
      (node (ref "CN17") (pin "1") (pinfunction "D3_1") (pintype "unspecified"))
    )
    (net (code "94") (name "unconnected-(CN17-GND-Pad6)") (class "Default")
      (node (ref "CN17") (pin "6") (pinfunction "GND_6") (pintype "unspecified"))
    )
    (net (code "95") (name "unconnected-(CN21-D0-Pad3)") (class "Default")
      (node (ref "CN21") (pin "3") (pinfunction "D0_3") (pintype "unspecified"))
    )
    (net (code "96") (name "unconnected-(CN21-D1-Pad4)") (class "Default")
      (node (ref "CN21") (pin "4") (pinfunction "D1_4") (pintype "unspecified"))
    )
    (net (code "97") (name "unconnected-(CN21-D2-Pad5)") (class "Default")
      (node (ref "CN21") (pin "5") (pinfunction "D2_5") (pintype "unspecified"))
    )
    (net (code "98") (name "unconnected-(CN21-D3-Pad6)") (class "Default")
      (node (ref "CN21") (pin "6") (pinfunction "D3_6") (pintype "unspecified"))
    )
    (net (code "99") (name "unconnected-(CN21-D4-Pad7)") (class "Default")
      (node (ref "CN21") (pin "7") (pinfunction "D4_7") (pintype "unspecified"))
    )
    (net (code "100") (name "unconnected-(CN21-D5-Pad8)") (class "Default")
      (node (ref "CN21") (pin "8") (pinfunction "D5_8") (pintype "unspecified"))
    )
    (net (code "101") (name "unconnected-(CN21-D6-Pad9)") (class "Default")
      (node (ref "CN21") (pin "9") (pinfunction "D6_9") (pintype "unspecified"))
    )
    (net (code "102") (name "unconnected-(CN21-D7-Pad10)") (class "Default")
      (node (ref "CN21") (pin "10") (pinfunction "D7_10") (pintype "unspecified"))
    )
    (net (code "103") (name "unconnected-(CN21-NC-Pad11)") (class "Default")
      (node (ref "CN21") (pin "11") (pinfunction "NC_11") (pintype "unspecified+no_connect"))
    )
    (net (code "104") (name "unconnected-(IC0-+5V-Pad11)") (class "Default")
      (node (ref "IC0") (pin "11") (pinfunction "+5V_11") (pintype "passive"))
    )
    (net (code "105") (name "unconnected-(IC0-A0-Pad30)") (class "Default")
      (node (ref "IC0") (pin "30") (pinfunction "A0_30") (pintype "output"))
    )
    (net (code "106") (name "unconnected-(IC0-A1-Pad31)") (class "Default")
      (node (ref "IC0") (pin "31") (pinfunction "A1_31") (pintype "output"))
    )
    (net (code "107") (name "unconnected-(IC0-A2-Pad32)") (class "Default")
      (node (ref "IC0") (pin "32") (pinfunction "A2_32") (pintype "output"))
    )
    (net (code "108") (name "unconnected-(IC0-A3-Pad33)") (class "Default")
      (node (ref "IC0") (pin "33") (pinfunction "A3_33") (pintype "output"))
    )
    (net (code "109") (name "unconnected-(IC0-A5-Pad35)") (class "Default")
      (node (ref "IC0") (pin "35") (pinfunction "A5_35") (pintype "output"))
    )
    (net (code "110") (name "unconnected-(IC0-A7-Pad37)") (class "Default")
      (node (ref "IC0") (pin "37") (pinfunction "A7_37") (pintype "output"))
    )
    (net (code "111") (name "unconnected-(IC0-A8-Pad38)") (class "Default")
      (node (ref "IC0") (pin "38") (pinfunction "A8_38") (pintype "output"))
    )
    (net (code "112") (name "unconnected-(IC0-A9-Pad39)") (class "Default")
      (node (ref "IC0") (pin "39") (pinfunction "A9_39") (pintype "output"))
    )
    (net (code "113") (name "unconnected-(IC0-A10-Pad40)") (class "Default")
      (node (ref "IC0") (pin "40") (pinfunction "A10_40") (pintype "output"))
    )
    (net (code "114") (name "unconnected-(IC0-A11-Pad1)") (class "Default")
      (node (ref "IC0") (pin "1") (pinfunction "A11_1") (pintype "output"))
    )
    (net (code "115") (name "unconnected-(IC0-A12-Pad2)") (class "Default")
      (node (ref "IC0") (pin "2") (pinfunction "A12_2") (pintype "output"))
    )
    (net (code "116") (name "unconnected-(IC0-A13-Pad3)") (class "Default")
      (node (ref "IC0") (pin "3") (pinfunction "A13_3") (pintype "output"))
    )
    (net (code "117") (name "unconnected-(IC0-BUSACK_(OUT)-Pad23)") (class "Default")
      (node (ref "IC0") (pin "23") (pinfunction "BUSACK_(OUT)_23") (pintype "output+no_connect"))
    )
    (net (code "118") (name "unconnected-(IC0-D0-Pad14)") (class "Default")
      (node (ref "IC0") (pin "14") (pinfunction "D0_14") (pintype "bidirectional"))
    )
    (net (code "119") (name "unconnected-(IC0-D1-Pad15)") (class "Default")
      (node (ref "IC0") (pin "15") (pinfunction "D1_15") (pintype "bidirectional"))
    )
    (net (code "120") (name "unconnected-(IC0-D2-Pad12)") (class "Default")
      (node (ref "IC0") (pin "12") (pinfunction "D2_12") (pintype "bidirectional"))
    )
    (net (code "121") (name "unconnected-(IC0-D3-Pad8)") (class "Default")
      (node (ref "IC0") (pin "8") (pinfunction "D3_8") (pintype "bidirectional"))
    )
    (net (code "122") (name "unconnected-(IC0-D4-Pad7)") (class "Default")
      (node (ref "IC0") (pin "7") (pinfunction "D4_7") (pintype "bidirectional"))
    )
    (net (code "123") (name "unconnected-(IC0-D5-Pad9)") (class "Default")
      (node (ref "IC0") (pin "9") (pinfunction "D5_9") (pintype "bidirectional"))
    )
    (net (code "124") (name "unconnected-(IC0-D6-Pad10)") (class "Default")
      (node (ref "IC0") (pin "10") (pinfunction "D6_10") (pintype "bidirectional"))
    )
    (net (code "125") (name "unconnected-(IC0-D7-Pad13)") (class "Default")
      (node (ref "IC0") (pin "13") (pinfunction "D7_13") (pintype "bidirectional"))
    )
    (net (code "126") (name "unconnected-(IC0-HALT_(OUT)-Pad18)") (class "Default")
      (node (ref "IC0") (pin "18") (pinfunction "HALT_(OUT)_18") (pintype "output+no_connect"))
    )
    (net (code "127") (name "unconnected-(IC0-RFSH_(OUT)-Pad28)") (class "Default")
      (node (ref "IC0") (pin "28") (pinfunction "RFSH_(OUT)_28") (pintype "output+no_connect"))
    )
    (net (code "128") (name "unconnected-(IC1-A2-Pad8)") (class "Default")
      (node (ref "IC1") (pin "8") (pinfunction "A2_8") (pintype "unspecified"))
    )
    (net (code "129") (name "unconnected-(IC1-A3-Pad7)") (class "Default")
      (node (ref "IC1") (pin "7") (pinfunction "A3_7") (pintype "unspecified"))
    )
    (net (code "130") (name "unconnected-(IC1-A4-Pad6)") (class "Default")
      (node (ref "IC1") (pin "6") (pinfunction "A4_6") (pintype "unspecified"))
    )
    (net (code "131") (name "unconnected-(IC1-A6-Pad4)") (class "Default")
      (node (ref "IC1") (pin "4") (pinfunction "A6_4") (pintype "unspecified"))
    )
    (net (code "132") (name "unconnected-(IC1-A7-Pad3)") (class "Default")
      (node (ref "IC1") (pin "3") (pinfunction "A7_3") (pintype "unspecified"))
    )
    (net (code "133") (name "unconnected-(IC1-A8-Pad25)") (class "Default")
      (node (ref "IC1") (pin "25") (pinfunction "A8_25") (pintype "unspecified"))
    )
    (net (code "134") (name "unconnected-(IC1-A9-Pad24)") (class "Default")
      (node (ref "IC1") (pin "24") (pinfunction "A9_24") (pintype "unspecified"))
    )
    (net (code "135") (name "unconnected-(IC1-A10-Pad21)") (class "Default")
      (node (ref "IC1") (pin "21") (pinfunction "A10_21") (pintype "unspecified"))
    )
    (net (code "136") (name "unconnected-(IC1-A11-Pad23)") (class "Default")
      (node (ref "IC1") (pin "23") (pinfunction "A11_23") (pintype "unspecified"))
    )
    (net (code "137") (name "unconnected-(IC1-A13-Pad26)") (class "Default")
      (node (ref "IC1") (pin "26") (pinfunction "A13_26") (pintype "unspecified"))
    )
    (net (code "138") (name "unconnected-(IC1-GND-Pad14)") (class "Default")
      (node (ref "IC1") (pin "14") (pinfunction "GND_14") (pintype "unspecified"))
    )
    (net (code "139") (name "unconnected-(IC1-O0-Pad11)") (class "Default")
      (node (ref "IC1") (pin "11") (pinfunction "O0_11") (pintype "unspecified"))
    )
    (net (code "140") (name "unconnected-(IC1-O1-Pad12)") (class "Default")
      (node (ref "IC1") (pin "12") (pinfunction "O1_12") (pintype "unspecified"))
    )
    (net (code "141") (name "unconnected-(IC1-O2-Pad13)") (class "Default")
      (node (ref "IC1") (pin "13") (pinfunction "O2_13") (pintype "unspecified"))
    )
    (net (code "142") (name "unconnected-(IC1-O3-Pad15)") (class "Default")
      (node (ref "IC1") (pin "15") (pinfunction "O3_15") (pintype "unspecified"))
    )
    (net (code "143") (name "unconnected-(IC1-O4-Pad16)") (class "Default")
      (node (ref "IC1") (pin "16") (pinfunction "O4_16") (pintype "unspecified"))
    )
    (net (code "144") (name "unconnected-(IC1-O5-Pad17)") (class "Default")
      (node (ref "IC1") (pin "17") (pinfunction "O5_17") (pintype "unspecified"))
    )
    (net (code "145") (name "unconnected-(IC1-O6-Pad18)") (class "Default")
      (node (ref "IC1") (pin "18") (pinfunction "O6_18") (pintype "unspecified"))
    )
    (net (code "146") (name "unconnected-(IC1-O7-Pad19)") (class "Default")
      (node (ref "IC1") (pin "19") (pinfunction "O7_19") (pintype "unspecified"))
    )
    (net (code "147") (name "unconnected-(IC1-VCC-Pad28)") (class "Default")
      (node (ref "IC1") (pin "28") (pinfunction "VCC_28") (pintype "unspecified"))
    )
    (net (code "148") (name "unconnected-(IC2-A0-Pad10)") (class "Default")
      (node (ref "IC2") (pin "10") (pinfunction "A0_10") (pintype "unspecified"))
    )
    (net (code "149") (name "unconnected-(IC2-A1-Pad9)") (class "Default")
      (node (ref "IC2") (pin "9") (pinfunction "A1_9") (pintype "unspecified"))
    )
    (net (code "150") (name "unconnected-(IC2-A2-Pad8)") (class "Default")
      (node (ref "IC2") (pin "8") (pinfunction "A2_8") (pintype "unspecified"))
    )
    (net (code "151") (name "unconnected-(IC2-A3-Pad7)") (class "Default")
      (node (ref "IC2") (pin "7") (pinfunction "A3_7") (pintype "unspecified"))
    )
    (net (code "152") (name "unconnected-(IC2-A4-Pad6)") (class "Default")
      (node (ref "IC2") (pin "6") (pinfunction "A4_6") (pintype "unspecified"))
    )
    (net (code "153") (name "unconnected-(IC2-A5-Pad5)") (class "Default")
      (node (ref "IC2") (pin "5") (pinfunction "A5_5") (pintype "unspecified"))
    )
    (net (code "154") (name "unconnected-(IC2-A6-Pad4)") (class "Default")
      (node (ref "IC2") (pin "4") (pinfunction "A6_4") (pintype "unspecified"))
    )
    (net (code "155") (name "unconnected-(IC2-A7-Pad3)") (class "Default")
      (node (ref "IC2") (pin "3") (pinfunction "A7_3") (pintype "unspecified"))
    )
    (net (code "156") (name "unconnected-(IC2-A8-Pad25)") (class "Default")
      (node (ref "IC2") (pin "25") (pinfunction "A8_25") (pintype "unspecified"))
    )
    (net (code "157") (name "unconnected-(IC2-A9-Pad24)") (class "Default")
      (node (ref "IC2") (pin "24") (pinfunction "A9_24") (pintype "unspecified"))
    )
    (net (code "158") (name "unconnected-(IC2-A10-Pad21)") (class "Default")
      (node (ref "IC2") (pin "21") (pinfunction "A10_21") (pintype "unspecified"))
    )
    (net (code "159") (name "unconnected-(IC2-A11-Pad23)") (class "Default")
      (node (ref "IC2") (pin "23") (pinfunction "A11_23") (pintype "unspecified"))
    )
    (net (code "160") (name "unconnected-(IC2-A12-Pad2)") (class "Default")
      (node (ref "IC2") (pin "2") (pinfunction "A12_2") (pintype "unspecified"))
    )
    (net (code "161") (name "unconnected-(IC2-D0-Pad11)") (class "Default")
      (node (ref "IC2") (pin "11") (pinfunction "D0_11") (pintype "unspecified"))
    )
    (net (code "162") (name "unconnected-(IC2-D1-Pad12)") (class "Default")
      (node (ref "IC2") (pin "12") (pinfunction "D1_12") (pintype "unspecified"))
    )
    (net (code "163") (name "unconnected-(IC2-D2-Pad13)") (class "Default")
      (node (ref "IC2") (pin "13") (pinfunction "D2_13") (pintype "unspecified"))
    )
    (net (code "164") (name "unconnected-(IC2-D3-Pad15)") (class "Default")
      (node (ref "IC2") (pin "15") (pinfunction "D3_15") (pintype "unspecified"))
    )
    (net (code "165") (name "unconnected-(IC2-D4-Pad16)") (class "Default")
      (node (ref "IC2") (pin "16") (pinfunction "D4_16") (pintype "unspecified"))
    )
    (net (code "166") (name "unconnected-(IC2-D5-Pad17)") (class "Default")
      (node (ref "IC2") (pin "17") (pinfunction "D5_17") (pintype "unspecified"))
    )
    (net (code "167") (name "unconnected-(IC2-D6-Pad18)") (class "Default")
      (node (ref "IC2") (pin "18") (pinfunction "D6_18") (pintype "unspecified"))
    )
    (net (code "168") (name "unconnected-(IC2-D7-Pad19)") (class "Default")
      (node (ref "IC2") (pin "19") (pinfunction "D7_19") (pintype "unspecified"))
    )
    (net (code "169") (name "unconnected-(IC2-VSS-Pad14)") (class "Default")
      (node (ref "IC2") (pin "14") (pinfunction "VSS_14") (pintype "unspecified"))
    )
    (net (code "170") (name "unconnected-(IC5-A0-Pad1)") (class "Default")
      (node (ref "IC5") (pin "1") (pinfunction "A0_1") (pintype "unspecified"))
    )
    (net (code "171") (name "unconnected-(IC5-A1-Pad2)") (class "Default")
      (node (ref "IC5") (pin "2") (pinfunction "A1_2") (pintype "unspecified"))
    )
    (net (code "172") (name "unconnected-(IC5-A2-Pad3)") (class "Default")
      (node (ref "IC5") (pin "3") (pinfunction "A2_3") (pintype "unspecified"))
    )
    (net (code "173") (name "unconnected-(IC5-GND-Pad8)") (class "Default")
      (node (ref "IC5") (pin "8") (pinfunction "GND_8") (pintype "unspecified"))
    )
    (net (code "174") (name "unconnected-(IC5-VCC-Pad16)") (class "Default")
      (node (ref "IC5") (pin "16") (pinfunction "VCC_16") (pintype "unspecified"))
    )
    (net (code "175") (name "unconnected-(IC5-Y3-Pad12)") (class "Default")
      (node (ref "IC5") (pin "12") (pinfunction "Y3_12") (pintype "unspecified+no_connect"))
    )
    (net (code "176") (name "unconnected-(IC5-Y4-Pad11)") (class "Default")
      (node (ref "IC5") (pin "11") (pinfunction "Y4_11") (pintype "unspecified+no_connect"))
    )
    (net (code "177") (name "unconnected-(IC5-Y5-Pad10)") (class "Default")
      (node (ref "IC5") (pin "10") (pinfunction "Y5_10") (pintype "unspecified+no_connect"))
    )
    (net (code "178") (name "unconnected-(IC5-Y6-Pad9)") (class "Default")
      (node (ref "IC5") (pin "9") (pinfunction "Y6_9") (pintype "unspecified+no_connect"))
    )
    (net (code "179") (name "unconnected-(IC5-Y7-Pad7)") (class "Default")
      (node (ref "IC5") (pin "7") (pinfunction "Y7_7") (pintype "unspecified+no_connect"))
    )
    (net (code "180") (name "unconnected-(IC7-GND-Pad7)") (class "Default")
      (node (ref "IC7") (pin "7") (pinfunction "GND_7") (pintype "unspecified"))
    )
    (net (code "181") (name "unconnected-(IC7-VCC-Pad14)") (class "Default")
      (node (ref "IC7") (pin "14") (pinfunction "VCC_14") (pintype "unspecified"))
    )
    (net (code "182") (name "unconnected-(IC8-GND-Pad7)") (class "Default")
      (node (ref "IC8") (pin "7") (pinfunction "GND_7") (pintype "unspecified"))
    )
    (net (code "183") (name "unconnected-(IC8-VCC-Pad14)") (class "Default")
      (node (ref "IC8") (pin "14") (pinfunction "VCC_14") (pintype "unspecified"))
    )
    (net (code "184") (name "unconnected-(IC9-GND-Pad7)") (class "Default")
      (node (ref "IC9") (pin "7") (pinfunction "GND_7") (pintype "passive"))
    )
    (net (code "185") (name "unconnected-(IC9-VCC-Pad14)") (class "Default")
      (node (ref "IC9") (pin "14") (pinfunction "VCC_14") (pintype "passive"))
    )
    (net (code "186") (name "unconnected-(IC9_1-GND-Pad7)") (class "Default")
      (node (ref "IC9_1") (pin "7") (pinfunction "GND_7") (pintype "passive"))
    )
    (net (code "187") (name "unconnected-(IC9_1-VCC-Pad14)") (class "Default")
      (node (ref "IC9_1") (pin "14") (pinfunction "VCC_14") (pintype "passive"))
    )
    (net (code "188") (name "unconnected-(IC9_2-GND-Pad7)") (class "Default")
      (node (ref "IC9_2") (pin "7") (pinfunction "GND_7") (pintype "passive"))
    )
    (net (code "189") (name "unconnected-(IC9_2-VCC-Pad14)") (class "Default")
      (node (ref "IC9_2") (pin "14") (pinfunction "VCC_14") (pintype "passive"))
    )
    (net (code "190") (name "unconnected-(IC9_3-GND-Pad7)") (class "Default")
      (node (ref "IC9_3") (pin "7") (pinfunction "GND_7") (pintype "passive"))
    )
    (net (code "191") (name "unconnected-(IC9_3-VCC-Pad14)") (class "Default")
      (node (ref "IC9_3") (pin "14") (pinfunction "VCC_14") (pintype "passive"))
    )
    (net (code "192") (name "unconnected-(IC9_4-GND-Pad7)") (class "Default")
      (node (ref "IC9_4") (pin "7") (pinfunction "GND_7") (pintype "passive"))
    )
    (net (code "193") (name "unconnected-(IC9_4-VCC-Pad14)") (class "Default")
      (node (ref "IC9_4") (pin "14") (pinfunction "VCC_14") (pintype "passive"))
    )
    (net (code "194") (name "unconnected-(IC9_5-GND-Pad7)") (class "Default")
      (node (ref "IC9_5") (pin "7") (pinfunction "GND_7") (pintype "passive"))
    )
    (net (code "195") (name "unconnected-(IC11-GND-Pad7)") (class "Default")
      (node (ref "IC11") (pin "7") (pinfunction "GND_7") (pintype "unspecified"))
    )
    (net (code "196") (name "unconnected-(IC11-VCC-Pad14)") (class "Default")
      (node (ref "IC11") (pin "14") (pinfunction "VCC_14") (pintype "unspecified"))
    )
    (net (code "197") (name "unconnected-(IC12-O_0-Pad9)") (class "Default")
      (node (ref "IC12") (pin "9") (pinfunction "O_0_9") (pintype "unspecified"))
    )
    (net (code "198") (name "unconnected-(IC12-O_1-Pad7)") (class "Default")
      (node (ref "IC12") (pin "7") (pinfunction "O_1_7") (pintype "unspecified+no_connect"))
    )
    (net (code "199") (name "unconnected-(IC12-O_2-Pad6)") (class "Default")
      (node (ref "IC12") (pin "6") (pinfunction "O_2_6") (pintype "unspecified+no_connect"))
    )
    (net (code "200") (name "unconnected-(IC12-O_3-Pad5)") (class "Default")
      (node (ref "IC12") (pin "5") (pinfunction "O_3_5") (pintype "unspecified+no_connect"))
    )
    (net (code "201") (name "unconnected-(IC12-O_4-Pad3)") (class "Default")
      (node (ref "IC12") (pin "3") (pinfunction "O_4_3") (pintype "unspecified+no_connect"))
    )
    (net (code "202") (name "unconnected-(IC12-O_5-Pad2)") (class "Default")
      (node (ref "IC12") (pin "2") (pinfunction "O_5_2") (pintype "unspecified+no_connect"))
    )
    (net (code "203") (name "unconnected-(IC12-O_6-Pad4)") (class "Default")
      (node (ref "IC12") (pin "4") (pinfunction "O_6_4") (pintype "unspecified+no_connect"))
    )
    (net (code "204") (name "unconnected-(IC12-O_7-Pad13)") (class "Default")
      (node (ref "IC12") (pin "13") (pinfunction "O_7_13") (pintype "unspecified+no_connect"))
    )
    (net (code "205") (name "unconnected-(IC12-O_8-Pad12)") (class "Default")
      (node (ref "IC12") (pin "12") (pinfunction "O_8_12") (pintype "unspecified+no_connect"))
    )
    (net (code "206") (name "unconnected-(IC12-O_10-Pad15)") (class "Default")
      (node (ref "IC12") (pin "15") (pinfunction "O_10_15") (pintype "unspecified+no_connect"))
    )
    (net (code "207") (name "unconnected-(IC12-VDD-Pad16)") (class "Default")
      (node (ref "IC12") (pin "16") (pinfunction "VDD_16") (pintype "unspecified"))
    )
    (net (code "208") (name "unconnected-(IC13-GND-Pad7)") (class "Default")
      (node (ref "IC13") (pin "7") (pinfunction "GND_7") (pintype "unspecified"))
    )
    (net (code "209") (name "unconnected-(IC13-N.C.-Pad8)") (class "Default")
      (node (ref "IC13") (pin "8") (pinfunction "N.C._8") (pintype "unspecified+no_connect"))
    )
    (net (code "210") (name "unconnected-(IC13-N.C.-Pad10)") (class "Default")
      (node (ref "IC13") (pin "10") (pinfunction "N.C._10") (pintype "unspecified+no_connect"))
    )
    (net (code "211") (name "unconnected-(IC13-N.C.-Pad13)") (class "Default")
      (node (ref "IC13") (pin "13") (pinfunction "N.C._13") (pintype "unspecified+no_connect"))
    )
    (net (code "212") (name "unconnected-(IC13-Q1-Pad12)") (class "Default")
      (node (ref "IC13") (pin "12") (pinfunction "Q1_12") (pintype "unspecified+no_connect"))
    )
    (net (code "213") (name "unconnected-(IC13-Q2-Pad11)") (class "Default")
      (node (ref "IC13") (pin "11") (pinfunction "Q2_11") (pintype "unspecified+no_connect"))
    )
    (net (code "214") (name "unconnected-(IC13-Q3-Pad9)") (class "Default")
      (node (ref "IC13") (pin "9") (pinfunction "Q3_9") (pintype "unspecified+no_connect"))
    )
    (net (code "215") (name "unconnected-(IC13-Q4-Pad6)") (class "Default")
      (node (ref "IC13") (pin "6") (pinfunction "Q4_6") (pintype "unspecified+no_connect"))
    )
    (net (code "216") (name "unconnected-(IC13-Q6-Pad4)") (class "Default")
      (node (ref "IC13") (pin "4") (pinfunction "Q6_4") (pintype "unspecified+no_connect"))
    )
    (net (code "217") (name "unconnected-(IC13-Q7-Pad3)") (class "Default")
      (node (ref "IC13") (pin "3") (pinfunction "Q7_3") (pintype "unspecified+no_connect"))
    )
    (net (code "218") (name "unconnected-(IC15-A0-Pad9)") (class "Default")
      (node (ref "IC15") (pin "9") (pinfunction "A0_9") (pintype "unspecified"))
    )
    (net (code "219") (name "unconnected-(IC15-A1-Pad8)") (class "Default")
      (node (ref "IC15") (pin "8") (pinfunction "A1_8") (pintype "unspecified"))
    )
    (net (code "220") (name "unconnected-(IC15-D0-Pad34)") (class "Default")
      (node (ref "IC15") (pin "34") (pinfunction "D0_34") (pintype "unspecified"))
    )
    (net (code "221") (name "unconnected-(IC15-D1-Pad33)") (class "Default")
      (node (ref "IC15") (pin "33") (pinfunction "D1_33") (pintype "unspecified"))
    )
    (net (code "222") (name "unconnected-(IC15-D2-Pad32)") (class "Default")
      (node (ref "IC15") (pin "32") (pinfunction "D2_32") (pintype "unspecified"))
    )
    (net (code "223") (name "unconnected-(IC15-D3-Pad31)") (class "Default")
      (node (ref "IC15") (pin "31") (pinfunction "D3_31") (pintype "unspecified"))
    )
    (net (code "224") (name "unconnected-(IC15-D4-Pad30)") (class "Default")
      (node (ref "IC15") (pin "30") (pinfunction "D4_30") (pintype "unspecified"))
    )
    (net (code "225") (name "unconnected-(IC15-D5-Pad29)") (class "Default")
      (node (ref "IC15") (pin "29") (pinfunction "D5_29") (pintype "unspecified"))
    )
    (net (code "226") (name "unconnected-(IC15-D6-Pad28)") (class "Default")
      (node (ref "IC15") (pin "28") (pinfunction "D6_28") (pintype "unspecified"))
    )
    (net (code "227") (name "unconnected-(IC15-D7-Pad27)") (class "Default")
      (node (ref "IC15") (pin "27") (pinfunction "D7_27") (pintype "unspecified"))
    )
    (net (code "228") (name "unconnected-(IC15-PB6-Pad24)") (class "Default")
      (node (ref "IC15") (pin "24") (pinfunction "PB6_24") (pintype "unspecified+no_connect"))
    )
    (net (code "229") (name "unconnected-(IC15-PC4-Pad13)") (class "Default")
      (node (ref "IC15") (pin "13") (pinfunction "PC4_13") (pintype "unspecified+no_connect"))
    )
    (net (code "230") (name "unconnected-(IC15-PC5-Pad12)") (class "Default")
      (node (ref "IC15") (pin "12") (pinfunction "PC5_12") (pintype "unspecified+no_connect"))
    )
    (net (code "231") (name "unconnected-(IC15-PC6-Pad11)") (class "Default")
      (node (ref "IC15") (pin "11") (pinfunction "PC6_11") (pintype "unspecified+no_connect"))
    )
    (net (code "232") (name "unconnected-(IC15-PC7-Pad10)") (class "Default")
      (node (ref "IC15") (pin "10") (pinfunction "PC7_10") (pintype "unspecified+no_connect"))
    )
    (net (code "233") (name "unconnected-(IC15-Vcc-Pad26)") (class "Default")
      (node (ref "IC15") (pin "26") (pinfunction "Vcc_26") (pintype "unspecified"))
    )
    (net (code "234") (name "unconnected-(IC15-Vss-Pad7)") (class "Default")
      (node (ref "IC15") (pin "7") (pinfunction "Vss_7") (pintype "unspecified"))
    )
    (net (code "235") (name "unconnected-(IC16-GND-Pad7)") (class "Default")
      (node (ref "IC16") (pin "7") (pinfunction "GND_7") (pintype "bidirectional"))
    )
    (net (code "236") (name "unconnected-(IC16-VCC-Pad14)") (class "Default")
      (node (ref "IC16") (pin "14") (pinfunction "VCC_14") (pintype "bidirectional"))
    )
    (net (code "237") (name "unconnected-(RL1-Pad2)") (class "Default")
      (node (ref "RL1") (pin "2") (pinfunction "2_2") (pintype "unspecified"))
    )
    (net (code "238") (name "unconnected-(SW1-Pad2)") (class "Default")
      (node (ref "SW1") (pin "2") (pinfunction "2_2") (pintype "unspecified"))
    )
    (net (code "239") (name "unconnected-(SW1-Pad4)") (class "Default")
      (node (ref "SW1") (pin "4") (pinfunction "4_4") (pintype "unspecified"))
    )
    (net (code "240") (name "unconnected-(SW2-Pad1)") (class "Default")
      (node (ref "SW2") (pin "1") (pinfunction "1_1") (pintype "unspecified"))
    )
    (net (code "241") (name "unconnected-(SW2-Pad3)") (class "Default")
      (node (ref "SW2") (pin "3") (pinfunction "3_3") (pintype "unspecified"))
    )
  )
)
